# SPv2.net
KiCad netlist of a schematic drawn in EAGLE
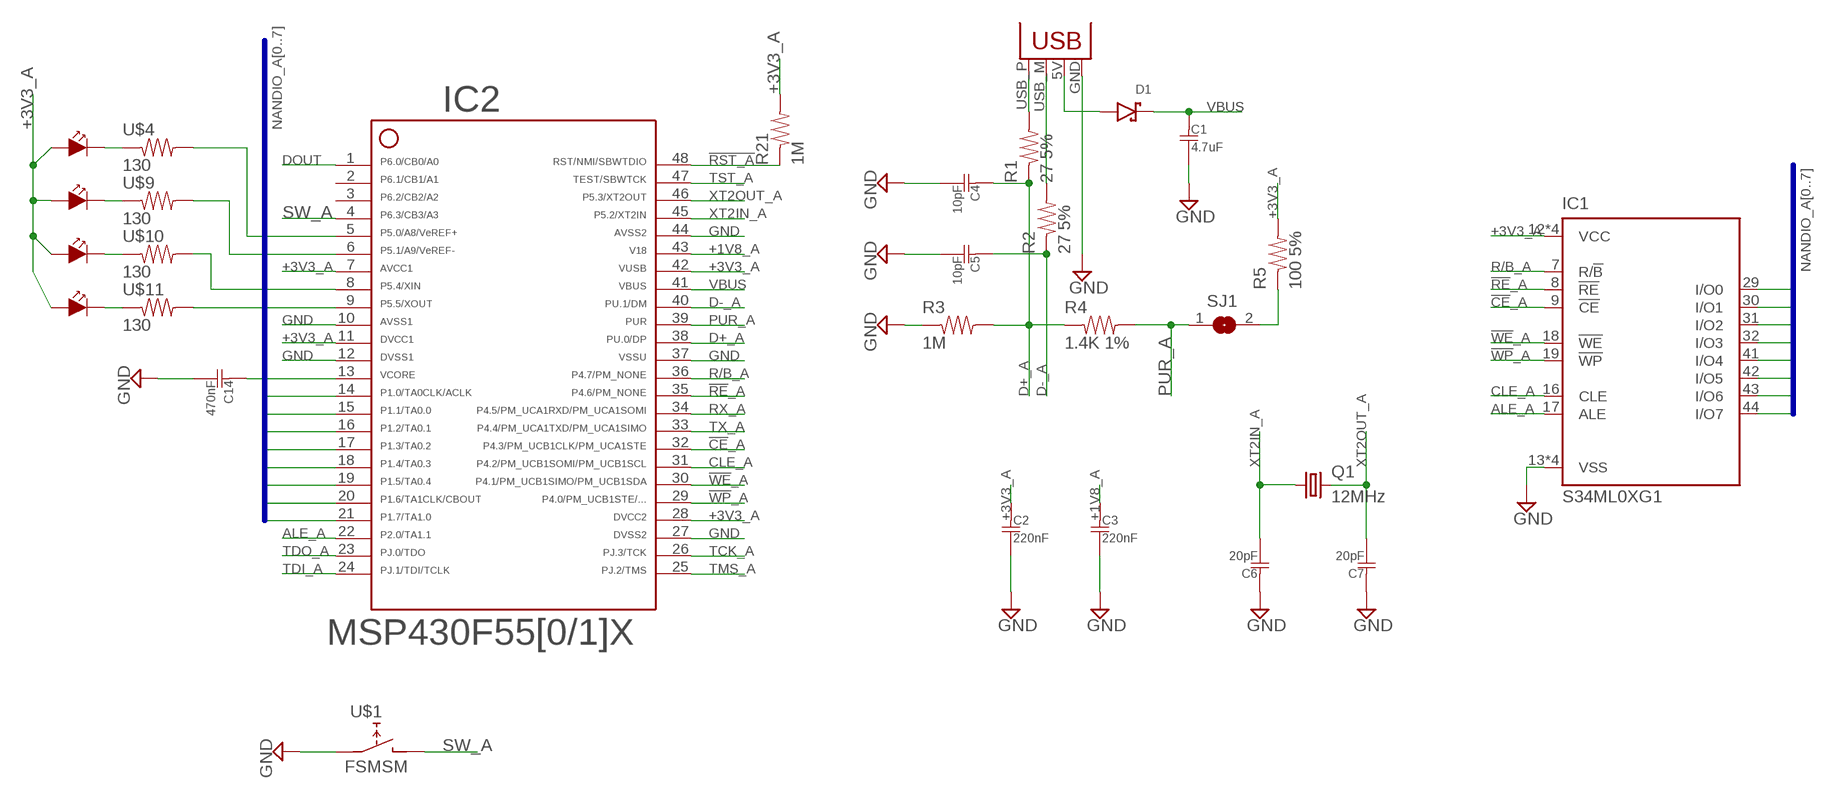
[diagram p0: schematic, sheet 1]
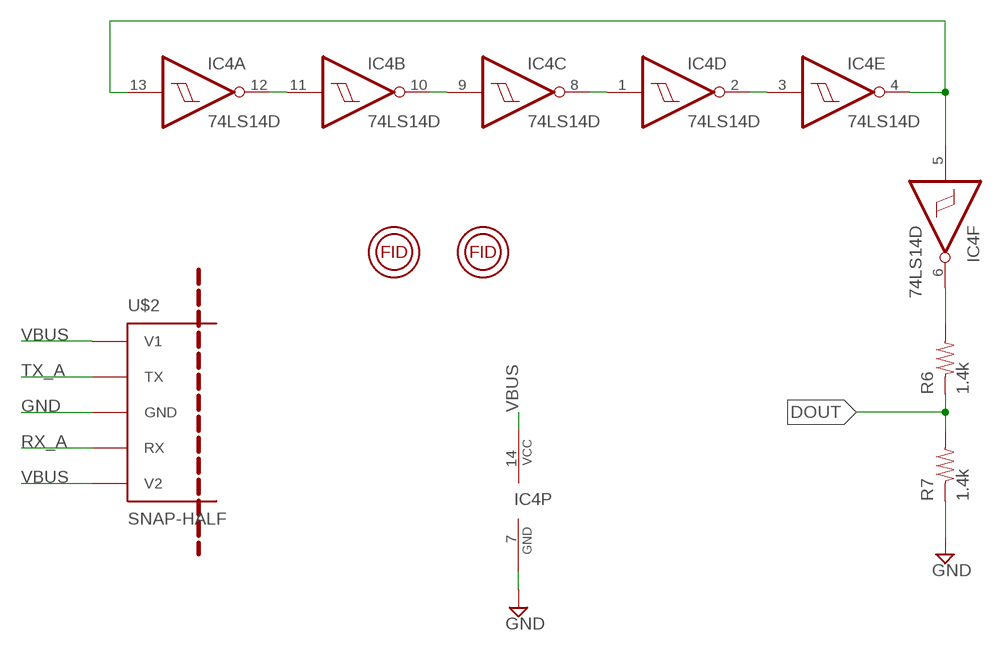
[diagram p1: schematic, sheet 2]

(export (version "E")
  (design (tool "Eeschema 10.0.6"))
  (components
    (comp (ref "IC4")
      (value "74LS14D")
      (footprint "eagle-import:SO14")
      (libsource (lib "eagle-import") (part "7414DLS"))
    )
    (comp (ref "R6")
      (value "1.4k")
      (footprint "eagle-import:R0805")
      (libsource (lib "eagle-import") (part "R0805"))
    )
    (comp (ref "R7")
      (value "1.4k")
      (footprint "eagle-import:R0805")
      (libsource (lib "eagle-import") (part "R0805"))
    )
    (comp (ref "U$2")
      (value "SNAP-HALF")
      (footprint "eagle-import:SNAP-HALF")
      (libsource (lib "eagle-import") (part "SNAP-HALF"))
    )
    (comp (ref "U$3")
      (value "FIDUCAL")
      (footprint "eagle-import:FIDUCAL")
      (libsource (lib "eagle-import") (part "FIDUCAL"))
    )
    (comp (ref "U$12")
      (value "FIDUCAL")
      (footprint "eagle-import:FIDUCAL")
      (libsource (lib "eagle-import") (part "FIDUCAL"))
    )
    (comp (ref "C1")
      (value "4.7uF")
      (footprint "eagle-import:R0805")
      (libsource (lib "eagle-import") (part "C0805"))
    )
    (comp (ref "C2")
      (value "220nF")
      (footprint "eagle-import:R0805")
      (libsource (lib "eagle-import") (part "C0805"))
    )
    (comp (ref "C3")
      (value "220nF")
      (footprint "eagle-import:R0805")
      (libsource (lib "eagle-import") (part "C0805"))
    )
    (comp (ref "C4")
      (value "10pF")
      (footprint "eagle-import:R0805")
      (libsource (lib "eagle-import") (part "C0805"))
    )
    (comp (ref "C5")
      (value "10pF")
      (footprint "eagle-import:R0805")
      (libsource (lib "eagle-import") (part "C0805"))
    )
    (comp (ref "C6")
      (value "20pF")
      (footprint "eagle-import:R0805")
      (libsource (lib "eagle-import") (part "C0805"))
    )
    (comp (ref "C7")
      (value "20pF")
      (footprint "eagle-import:R0805")
      (libsource (lib "eagle-import") (part "C0805"))
    )
    (comp (ref "C14")
      (value "470nF")
      (footprint "eagle-import:R0805")
      (libsource (lib "eagle-import") (part "C0805"))
    )
    (comp (ref "D1")
      (value "D-SCHOTTKY")
      (footprint "eagle-import:SOD123")
      (libsource (lib "eagle-import") (part "D-SCHOTTKY"))
    )
    (comp (ref "IC1")
      (value "S34ML0XG1")
      (footprint "eagle-import:TSOP48")
      (libsource (lib "eagle-import") (part "S34ML0XG1"))
    )
    (comp (ref "IC2")
      (value "F5508")
      (footprint "eagle-import:PT48")
      (libsource (lib "eagle-import") (part "F55[0/1]X---PT48"))
    )
    (comp (ref "JP1")
      (value "USBPCB")
      (footprint "eagle-import:USB-A-PCB")
      (libsource (lib "eagle-import") (part "USBPCB"))
    )
    (comp (ref "Q1")
      (value "12MHz")
      (footprint "eagle-import:CSM-3X")
      (libsource (lib "eagle-import") (part "CRYSTALCSM-3X"))
    )
    (comp (ref "R1")
      (value "27 5%")
      (footprint "eagle-import:R0805")
      (libsource (lib "eagle-import") (part "R0805"))
    )
    (comp (ref "R2")
      (value "27 5%")
      (footprint "eagle-import:R0805")
      (libsource (lib "eagle-import") (part "R0805"))
    )
    (comp (ref "R3")
      (value "1M")
      (footprint "eagle-import:R0805")
      (libsource (lib "eagle-import") (part "R0805"))
    )
    (comp (ref "R4")
      (value "1.4K 1%")
      (footprint "eagle-import:R0805")
      (libsource (lib "eagle-import") (part "R0805"))
    )
    (comp (ref "R5")
      (value "100 5%")
      (footprint "eagle-import:R0805")
      (libsource (lib "eagle-import") (part "R0805"))
    )
    (comp (ref "R21")
      (value "1M")
      (footprint "eagle-import:R0805")
      (libsource (lib "eagle-import") (part "R0805"))
    )
    (comp (ref "SJ1")
      (value "SJW")
      (footprint "eagle-import:SJW")
      (libsource (lib "eagle-import") (part "SJW"))
    )
    (comp (ref "U$1")
      (value "FSMSM")
      (footprint "eagle-import:FSMSM")
      (libsource (lib "eagle-import") (part "FSMSM"))
    )
    (comp (ref "U$4")
      (value "130")
      (footprint "eagle-import:R0805")
      (libsource (lib "eagle-import") (part "R0805"))
    )
    (comp (ref "U$5")
      (value "LED")
      (footprint "eagle-import:LED0805")
      (libsource (lib "eagle-import") (part "LED"))
    )
    (comp (ref "U$6")
      (value "LED")
      (footprint "eagle-import:LED0805")
      (libsource (lib "eagle-import") (part "LED"))
    )
    (comp (ref "U$7")
      (value "LED")
      (footprint "eagle-import:LED0805")
      (libsource (lib "eagle-import") (part "LED"))
    )
    (comp (ref "U$8")
      (value "LED")
      (footprint "eagle-import:LED0805")
      (libsource (lib "eagle-import") (part "LED"))
    )
    (comp (ref "U$9")
      (value "130")
      (footprint "eagle-import:R0805")
      (libsource (lib "eagle-import") (part "R0805"))
    )
    (comp (ref "U$10")
      (value "130")
      (footprint "eagle-import:R0805")
      (libsource (lib "eagle-import") (part "R0805"))
    )
    (comp (ref "U$11")
      (value "130")
      (footprint "eagle-import:R0805")
      (libsource (lib "eagle-import") (part "R0805"))
    )
  )
  (nets
    (net (code "1") (name "+1V8_A") (class "Default")
      (node (ref "C3") (pin "P$1") (pinfunction "1_P$1") (pintype "passive"))
      (node (ref "IC2") (pin "43") (pinfunction "43_43") (pintype "power_in"))
    )
    (net (code "2") (name "+3V3_A") (class "Default")
      (node (ref "C2") (pin "P$1") (pinfunction "1_P$1") (pintype "passive"))
      (node (ref "IC1") (pin "12") (pinfunction "VCC_12") (pintype "power_in"))
      (node (ref "IC1") (pin "34") (pinfunction "VCC_34") (pintype "power_in"))
      (node (ref "IC1") (pin "37") (pinfunction "VCC_37") (pintype "power_in"))
      (node (ref "IC1") (pin "39") (pinfunction "VCC_39") (pintype "power_in"))
      (node (ref "IC2") (pin "11") (pinfunction "11_11") (pintype "power_in"))
      (node (ref "IC2") (pin "28") (pinfunction "28_28") (pintype "power_in"))
      (node (ref "IC2") (pin "42") (pinfunction "42_42") (pintype "power_in"))
      (node (ref "IC2") (pin "7") (pinfunction "7_7") (pintype "power_in"))
      (node (ref "R21") (pin "P$2") (pinfunction "2_P$2") (pintype "passive"))
      (node (ref "R5") (pin "P$2") (pinfunction "2_P$2") (pintype "passive"))
      (node (ref "U$5") (pin "ANODE") (pinfunction "ANODE_ANODE") (pintype "passive"))
      (node (ref "U$6") (pin "ANODE") (pinfunction "ANODE_ANODE") (pintype "passive"))
      (node (ref "U$7") (pin "ANODE") (pinfunction "ANODE_ANODE") (pintype "passive"))
      (node (ref "U$8") (pin "ANODE") (pinfunction "ANODE_ANODE") (pintype "passive"))
    )
    (net (code "4") (name "ALE_A") (class "Default")
      (node (ref "IC1") (pin "17") (pinfunction "ALE_17") (pintype "input"))
      (node (ref "IC2") (pin "22") (pinfunction "22_22") (pintype "bidirectional"))
    )
    (net (code "5") (name "CLE_A") (class "Default")
      (node (ref "IC1") (pin "16") (pinfunction "CLE_16") (pintype "input"))
      (node (ref "IC2") (pin "31") (pinfunction "31_31") (pintype "bidirectional"))
    )
    (net (code "6") (name "D+_A") (class "Default")
      (node (ref "C4") (pin "P$1") (pinfunction "1_P$1") (pintype "passive"))
      (node (ref "IC2") (pin "38") (pinfunction "38_38") (pintype "bidirectional"))
      (node (ref "R1") (pin "P$1") (pinfunction "1_P$1") (pintype "passive"))
      (node (ref "R3") (pin "P$2") (pinfunction "2_P$2") (pintype "passive"))
      (node (ref "R4") (pin "P$1") (pinfunction "1_P$1") (pintype "passive"))
    )
    (net (code "7") (name "D-_A") (class "Default")
      (node (ref "C5") (pin "P$1") (pinfunction "1_P$1") (pintype "passive"))
      (node (ref "IC2") (pin "40") (pinfunction "40_40") (pintype "bidirectional"))
      (node (ref "R2") (pin "P$1") (pinfunction "1_P$1") (pintype "passive"))
    )
    (net (code "8") (name "DOUT") (class "Default")
      (node (ref "IC2") (pin "1") (pinfunction "1_1") (pintype "bidirectional"))
      (node (ref "R6") (pin "P$1") (pinfunction "1_P$1") (pintype "passive"))
      (node (ref "R7") (pin "P$2") (pinfunction "2_P$2") (pintype "passive"))
    )
    (net (code "9") (name "GND") (class "Default")
      (node (ref "C1") (pin "P$2") (pinfunction "2_P$2") (pintype "passive"))
      (node (ref "C14") (pin "P$2") (pinfunction "2_P$2") (pintype "passive"))
      (node (ref "C2") (pin "P$2") (pinfunction "2_P$2") (pintype "passive"))
      (node (ref "C3") (pin "P$2") (pinfunction "2_P$2") (pintype "passive"))
      (node (ref "C4") (pin "P$2") (pinfunction "2_P$2") (pintype "passive"))
      (node (ref "C5") (pin "P$2") (pinfunction "2_P$2") (pintype "passive"))
      (node (ref "C6") (pin "P$1") (pinfunction "1_P$1") (pintype "passive"))
      (node (ref "C7") (pin "P$1") (pinfunction "1_P$1") (pintype "passive"))
      (node (ref "IC1") (pin "13") (pinfunction "VSS_13") (pintype "power_in"))
      (node (ref "IC1") (pin "25") (pinfunction "VSS_25") (pintype "power_in"))
      (node (ref "IC1") (pin "36") (pinfunction "VSS_36") (pintype "power_in"))
      (node (ref "IC1") (pin "48") (pinfunction "VSS_48") (pintype "power_in"))
      (node (ref "IC2") (pin "10") (pinfunction "10_10") (pintype "power_in"))
      (node (ref "IC2") (pin "12") (pinfunction "12_12") (pintype "power_in"))
      (node (ref "IC2") (pin "27") (pinfunction "27_27") (pintype "power_in"))
      (node (ref "IC2") (pin "37") (pinfunction "37_37") (pintype "power_in"))
      (node (ref "IC2") (pin "44") (pinfunction "44_44") (pintype "power_in"))
      (node (ref "IC4") (pin "7") (pinfunction "GND_7") (pintype "power_in"))
      (node (ref "JP1") (pin "GND") (pinfunction "GND_GND") (pintype "bidirectional"))
      (node (ref "R3") (pin "P$1") (pinfunction "1_P$1") (pintype "passive"))
      (node (ref "R7") (pin "P$1") (pinfunction "1_P$1") (pintype "passive"))
      (node (ref "U$1") (pin "P$1") (pinfunction "A1_P$1") (pintype "passive"))
      (node (ref "U$2") (pin "P$3") (pinfunction "GND_P$3") (pintype "bidirectional"))
    )
    (net (code "10") (name "NANDIO_A0") (class "Default")
      (node (ref "IC1") (pin "29") (pinfunction "I/O0_29") (pintype "bidirectional"))
      (node (ref "IC2") (pin "14") (pinfunction "14_14") (pintype "bidirectional"))
    )
    (net (code "11") (name "NANDIO_A1") (class "Default")
      (node (ref "IC1") (pin "30") (pinfunction "I/O1_30") (pintype "bidirectional"))
      (node (ref "IC2") (pin "15") (pinfunction "15_15") (pintype "bidirectional"))
    )
    (net (code "12") (name "NANDIO_A2") (class "Default")
      (node (ref "IC1") (pin "31") (pinfunction "I/O2_31") (pintype "bidirectional"))
      (node (ref "IC2") (pin "16") (pinfunction "16_16") (pintype "bidirectional"))
    )
    (net (code "13") (name "NANDIO_A3") (class "Default")
      (node (ref "IC1") (pin "32") (pinfunction "I/O3_32") (pintype "bidirectional"))
      (node (ref "IC2") (pin "17") (pinfunction "17_17") (pintype "bidirectional"))
    )
    (net (code "14") (name "NANDIO_A4") (class "Default")
      (node (ref "IC1") (pin "41") (pinfunction "I/O4_41") (pintype "bidirectional"))
      (node (ref "IC2") (pin "18") (pinfunction "18_18") (pintype "bidirectional"))
    )
    (net (code "15") (name "NANDIO_A5") (class "Default")
      (node (ref "IC1") (pin "42") (pinfunction "I/O5_42") (pintype "bidirectional"))
      (node (ref "IC2") (pin "19") (pinfunction "19_19") (pintype "bidirectional"))
    )
    (net (code "16") (name "NANDIO_A6") (class "Default")
      (node (ref "IC1") (pin "43") (pinfunction "I/O6_43") (pintype "bidirectional"))
      (node (ref "IC2") (pin "20") (pinfunction "20_20") (pintype "bidirectional"))
    )
    (net (code "17") (name "NANDIO_A7") (class "Default")
      (node (ref "IC1") (pin "44") (pinfunction "I/O7_44") (pintype "bidirectional"))
      (node (ref "IC2") (pin "21") (pinfunction "21_21") (pintype "bidirectional"))
    )
    (net (code "18") (name "Net-(C14-1)") (class "Default")
      (node (ref "C14") (pin "P$1") (pinfunction "1_P$1") (pintype "passive"))
      (node (ref "IC2") (pin "13") (pinfunction "13_13") (pintype "power_in"))
    )
    (net (code "19") (name "Net-(IC4A-I)") (class "Default")
      (node (ref "IC4") (pin "13") (pinfunction "I_13") (pintype "input"))
      (node (ref "IC4") (pin "4") (pinfunction "O_4") (pintype "output"))
      (node (ref "IC4") (pin "5") (pinfunction "I_5") (pintype "input"))
    )
    (net (code "20") (name "Net-(IC4A-O)") (class "Default")
      (node (ref "IC4") (pin "11") (pinfunction "I_11") (pintype "input"))
      (node (ref "IC4") (pin "12") (pinfunction "O_12") (pintype "output"))
    )
    (net (code "21") (name "Net-(IC4B-O)") (class "Default")
      (node (ref "IC4") (pin "10") (pinfunction "O_10") (pintype "output"))
      (node (ref "IC4") (pin "9") (pinfunction "I_9") (pintype "input"))
    )
    (net (code "22") (name "Net-(IC4C-O)") (class "Default")
      (node (ref "IC4") (pin "1") (pinfunction "I_1") (pintype "input"))
      (node (ref "IC4") (pin "8") (pinfunction "O_8") (pintype "output"))
    )
    (net (code "23") (name "Net-(IC4D-O)") (class "Default")
      (node (ref "IC4") (pin "2") (pinfunction "O_2") (pintype "output"))
      (node (ref "IC4") (pin "3") (pinfunction "I_3") (pintype "input"))
    )
    (net (code "24") (name "Net-(IC4F-O)") (class "Default")
      (node (ref "IC4") (pin "6") (pinfunction "O_6") (pintype "output"))
      (node (ref "R6") (pin "P$2") (pinfunction "2_P$2") (pintype "passive"))
    )
    (net (code "25") (name "Net-(JP1-D+)") (class "Default")
      (node (ref "JP1") (pin "USB_P") (pinfunction "D+_USB_P") (pintype "bidirectional"))
      (node (ref "R1") (pin "P$2") (pinfunction "2_P$2") (pintype "passive"))
    )
    (net (code "26") (name "Net-(JP1-D-)") (class "Default")
      (node (ref "JP1") (pin "USB_M") (pinfunction "D-_USB_M") (pintype "bidirectional"))
      (node (ref "R2") (pin "P$2") (pinfunction "2_P$2") (pintype "passive"))
    )
    (net (code "27") (name "Net-(JP1-VBUS)") (class "Default")
      (node (ref "D1") (pin "ANODE") (pinfunction "ANODE_ANODE") (pintype "passive"))
      (node (ref "JP1") (pin "5V") (pinfunction "VBUS_5V") (pintype "bidirectional"))
    )
    (net (code "28") (name "Net-(R5-1)") (class "Default")
      (node (ref "R5") (pin "P$1") (pinfunction "1_P$1") (pintype "passive"))
      (node (ref "SJ1") (pin "2") (pinfunction "2_2") (pintype "passive"))
    )
    (net (code "29") (name "Net-(U$4-1)") (class "Default")
      (node (ref "U$4") (pin "P$1") (pinfunction "1_P$1") (pintype "passive"))
      (node (ref "U$5") (pin "CATHODE") (pinfunction "CATHODE_CATHODE") (pintype "passive"))
    )
    (net (code "30") (name "Net-(U$4-2)") (class "Default")
      (node (ref "IC2") (pin "5") (pinfunction "5_5") (pintype "bidirectional"))
      (node (ref "U$4") (pin "P$2") (pinfunction "2_P$2") (pintype "passive"))
    )
    (net (code "31") (name "Net-(U$9-1)") (class "Default")
      (node (ref "U$6") (pin "CATHODE") (pinfunction "CATHODE_CATHODE") (pintype "passive"))
      (node (ref "U$9") (pin "P$1") (pinfunction "1_P$1") (pintype "passive"))
    )
    (net (code "32") (name "Net-(U$9-2)") (class "Default")
      (node (ref "IC2") (pin "6") (pinfunction "6_6") (pintype "bidirectional"))
      (node (ref "U$9") (pin "P$2") (pinfunction "2_P$2") (pintype "passive"))
    )
    (net (code "33") (name "Net-(U$10-1)") (class "Default")
      (node (ref "U$10") (pin "P$1") (pinfunction "1_P$1") (pintype "passive"))
      (node (ref "U$7") (pin "CATHODE") (pinfunction "CATHODE_CATHODE") (pintype "passive"))
    )
    (net (code "34") (name "Net-(U$10-2)") (class "Default")
      (node (ref "IC2") (pin "8") (pinfunction "8_8") (pintype "bidirectional"))
      (node (ref "U$10") (pin "P$2") (pinfunction "2_P$2") (pintype "passive"))
    )
    (net (code "35") (name "Net-(U$11-1)") (class "Default")
      (node (ref "U$11") (pin "P$1") (pinfunction "1_P$1") (pintype "passive"))
      (node (ref "U$8") (pin "CATHODE") (pinfunction "CATHODE_CATHODE") (pintype "passive"))
    )
    (net (code "36") (name "Net-(U$11-2)") (class "Default")
      (node (ref "IC2") (pin "9") (pinfunction "9_9") (pintype "bidirectional"))
      (node (ref "U$11") (pin "P$2") (pinfunction "2_P$2") (pintype "passive"))
    )
    (net (code "37") (name "PUR_A") (class "Default")
      (node (ref "IC2") (pin "39") (pinfunction "39_39") (pintype "bidirectional"))
      (node (ref "R4") (pin "P$2") (pinfunction "2_P$2") (pintype "passive"))
      (node (ref "SJ1") (pin "1") (pinfunction "1_1") (pintype "passive"))
    )
    (net (code "38") (name "RX_A") (class "Default")
      (node (ref "IC2") (pin "34") (pinfunction "34_34") (pintype "bidirectional"))
      (node (ref "U$2") (pin "P$4") (pinfunction "RX_P$4") (pintype "bidirectional"))
    )
    (net (code "39") (name "R{slash}B_A") (class "Default")
      (node (ref "IC1") (pin "7") (pinfunction "R/~{B}_7") (pintype "input"))
      (node (ref "IC2") (pin "36") (pinfunction "36_36") (pintype "bidirectional"))
    )
    (net (code "40") (name "SW_A") (class "Default")
      (node (ref "IC2") (pin "4") (pinfunction "4_4") (pintype "bidirectional"))
      (node (ref "U$1") (pin "P$2") (pinfunction "B_P$2") (pintype "passive"))
    )
    (net (code "41") (name "TCK_A") (class "Default")
      (node (ref "IC2") (pin "26") (pinfunction "26_26") (pintype "bidirectional"))
    )
    (net (code "42") (name "TDI_A") (class "Default")
      (node (ref "IC2") (pin "24") (pinfunction "24_24") (pintype "bidirectional"))
    )
    (net (code "43") (name "TDO_A") (class "Default")
      (node (ref "IC2") (pin "23") (pinfunction "23_23") (pintype "bidirectional"))
    )
    (net (code "44") (name "TMS_A") (class "Default")
      (node (ref "IC2") (pin "25") (pinfunction "25_25") (pintype "bidirectional"))
    )
    (net (code "45") (name "TST_A") (class "Default")
      (node (ref "IC2") (pin "47") (pinfunction "47_47") (pintype "input"))
    )
    (net (code "46") (name "TX_A") (class "Default")
      (node (ref "IC2") (pin "33") (pinfunction "33_33") (pintype "bidirectional"))
      (node (ref "U$2") (pin "P$2") (pinfunction "TX_P$2") (pintype "bidirectional"))
    )
    (net (code "47") (name "VBUS") (class "Default")
      (node (ref "C1") (pin "P$1") (pinfunction "1_P$1") (pintype "passive"))
      (node (ref "D1") (pin "CATHODE") (pinfunction "CATHODE_CATHODE") (pintype "passive"))
      (node (ref "IC2") (pin "41") (pinfunction "41_41") (pintype "power_in"))
      (node (ref "IC4") (pin "14") (pinfunction "VCC_14") (pintype "power_in"))
      (node (ref "U$2") (pin "P$1") (pinfunction "V1_P$1") (pintype "bidirectional"))
      (node (ref "U$2") (pin "P$5") (pinfunction "V2_P$5") (pintype "bidirectional"))
    )
    (net (code "48") (name "XT2IN_A") (class "Default")
      (node (ref "C6") (pin "P$2") (pinfunction "2_P$2") (pintype "passive"))
      (node (ref "IC2") (pin "45") (pinfunction "45_45") (pintype "bidirectional"))
      (node (ref "Q1") (pin "P$1") (pinfunction "1_P$1") (pintype "passive"))
    )
    (net (code "49") (name "XT2OUT_A") (class "Default")
      (node (ref "C7") (pin "P$2") (pinfunction "2_P$2") (pintype "passive"))
      (node (ref "IC2") (pin "46") (pinfunction "46_46") (pintype "power_in"))
      (node (ref "Q1") (pin "P$2") (pinfunction "2_P$2") (pintype "passive"))
    )
    (net (code "50") (name "unconnected-(IC2-Pad2)") (class "Default")
      (node (ref "IC2") (pin "2") (pinfunction "2_2") (pintype "bidirectional"))
    )
    (net (code "51") (name "unconnected-(IC2-Pad3)") (class "Default")
      (node (ref "IC2") (pin "3") (pinfunction "3_3") (pintype "bidirectional"))
    )
    (net (code "52") (name "~{CE}_A") (class "Default")
      (node (ref "IC1") (pin "9") (pinfunction "~{CE}_9") (pintype "input"))
      (node (ref "IC2") (pin "32") (pinfunction "32_32") (pintype "bidirectional"))
    )
    (net (code "53") (name "~{RE}_A") (class "Default")
      (node (ref "IC1") (pin "8") (pinfunction "~{RE}_8") (pintype "input"))
      (node (ref "IC2") (pin "35") (pinfunction "35_35") (pintype "bidirectional"))
    )
    (net (code "54") (name "~{RST_A}") (class "Default")
      (node (ref "IC2") (pin "48") (pinfunction "48_48") (pintype "bidirectional"))
      (node (ref "R21") (pin "P$1") (pinfunction "1_P$1") (pintype "passive"))
    )
    (net (code "55") (name "~{WE}_A") (class "Default")
      (node (ref "IC1") (pin "18") (pinfunction "~{WE}_18") (pintype "input"))
      (node (ref "IC2") (pin "30") (pinfunction "30_30") (pintype "bidirectional"))
    )
    (net (code "56") (name "~{WP}_A") (class "Default")
      (node (ref "IC1") (pin "19") (pinfunction "~{WP}_19") (pintype "input"))
      (node (ref "IC2") (pin "29") (pinfunction "29_29") (pintype "bidirectional"))
    )
  )
)
